# E3.net
KiCad netlist of a schematic drawn in Altium Designer
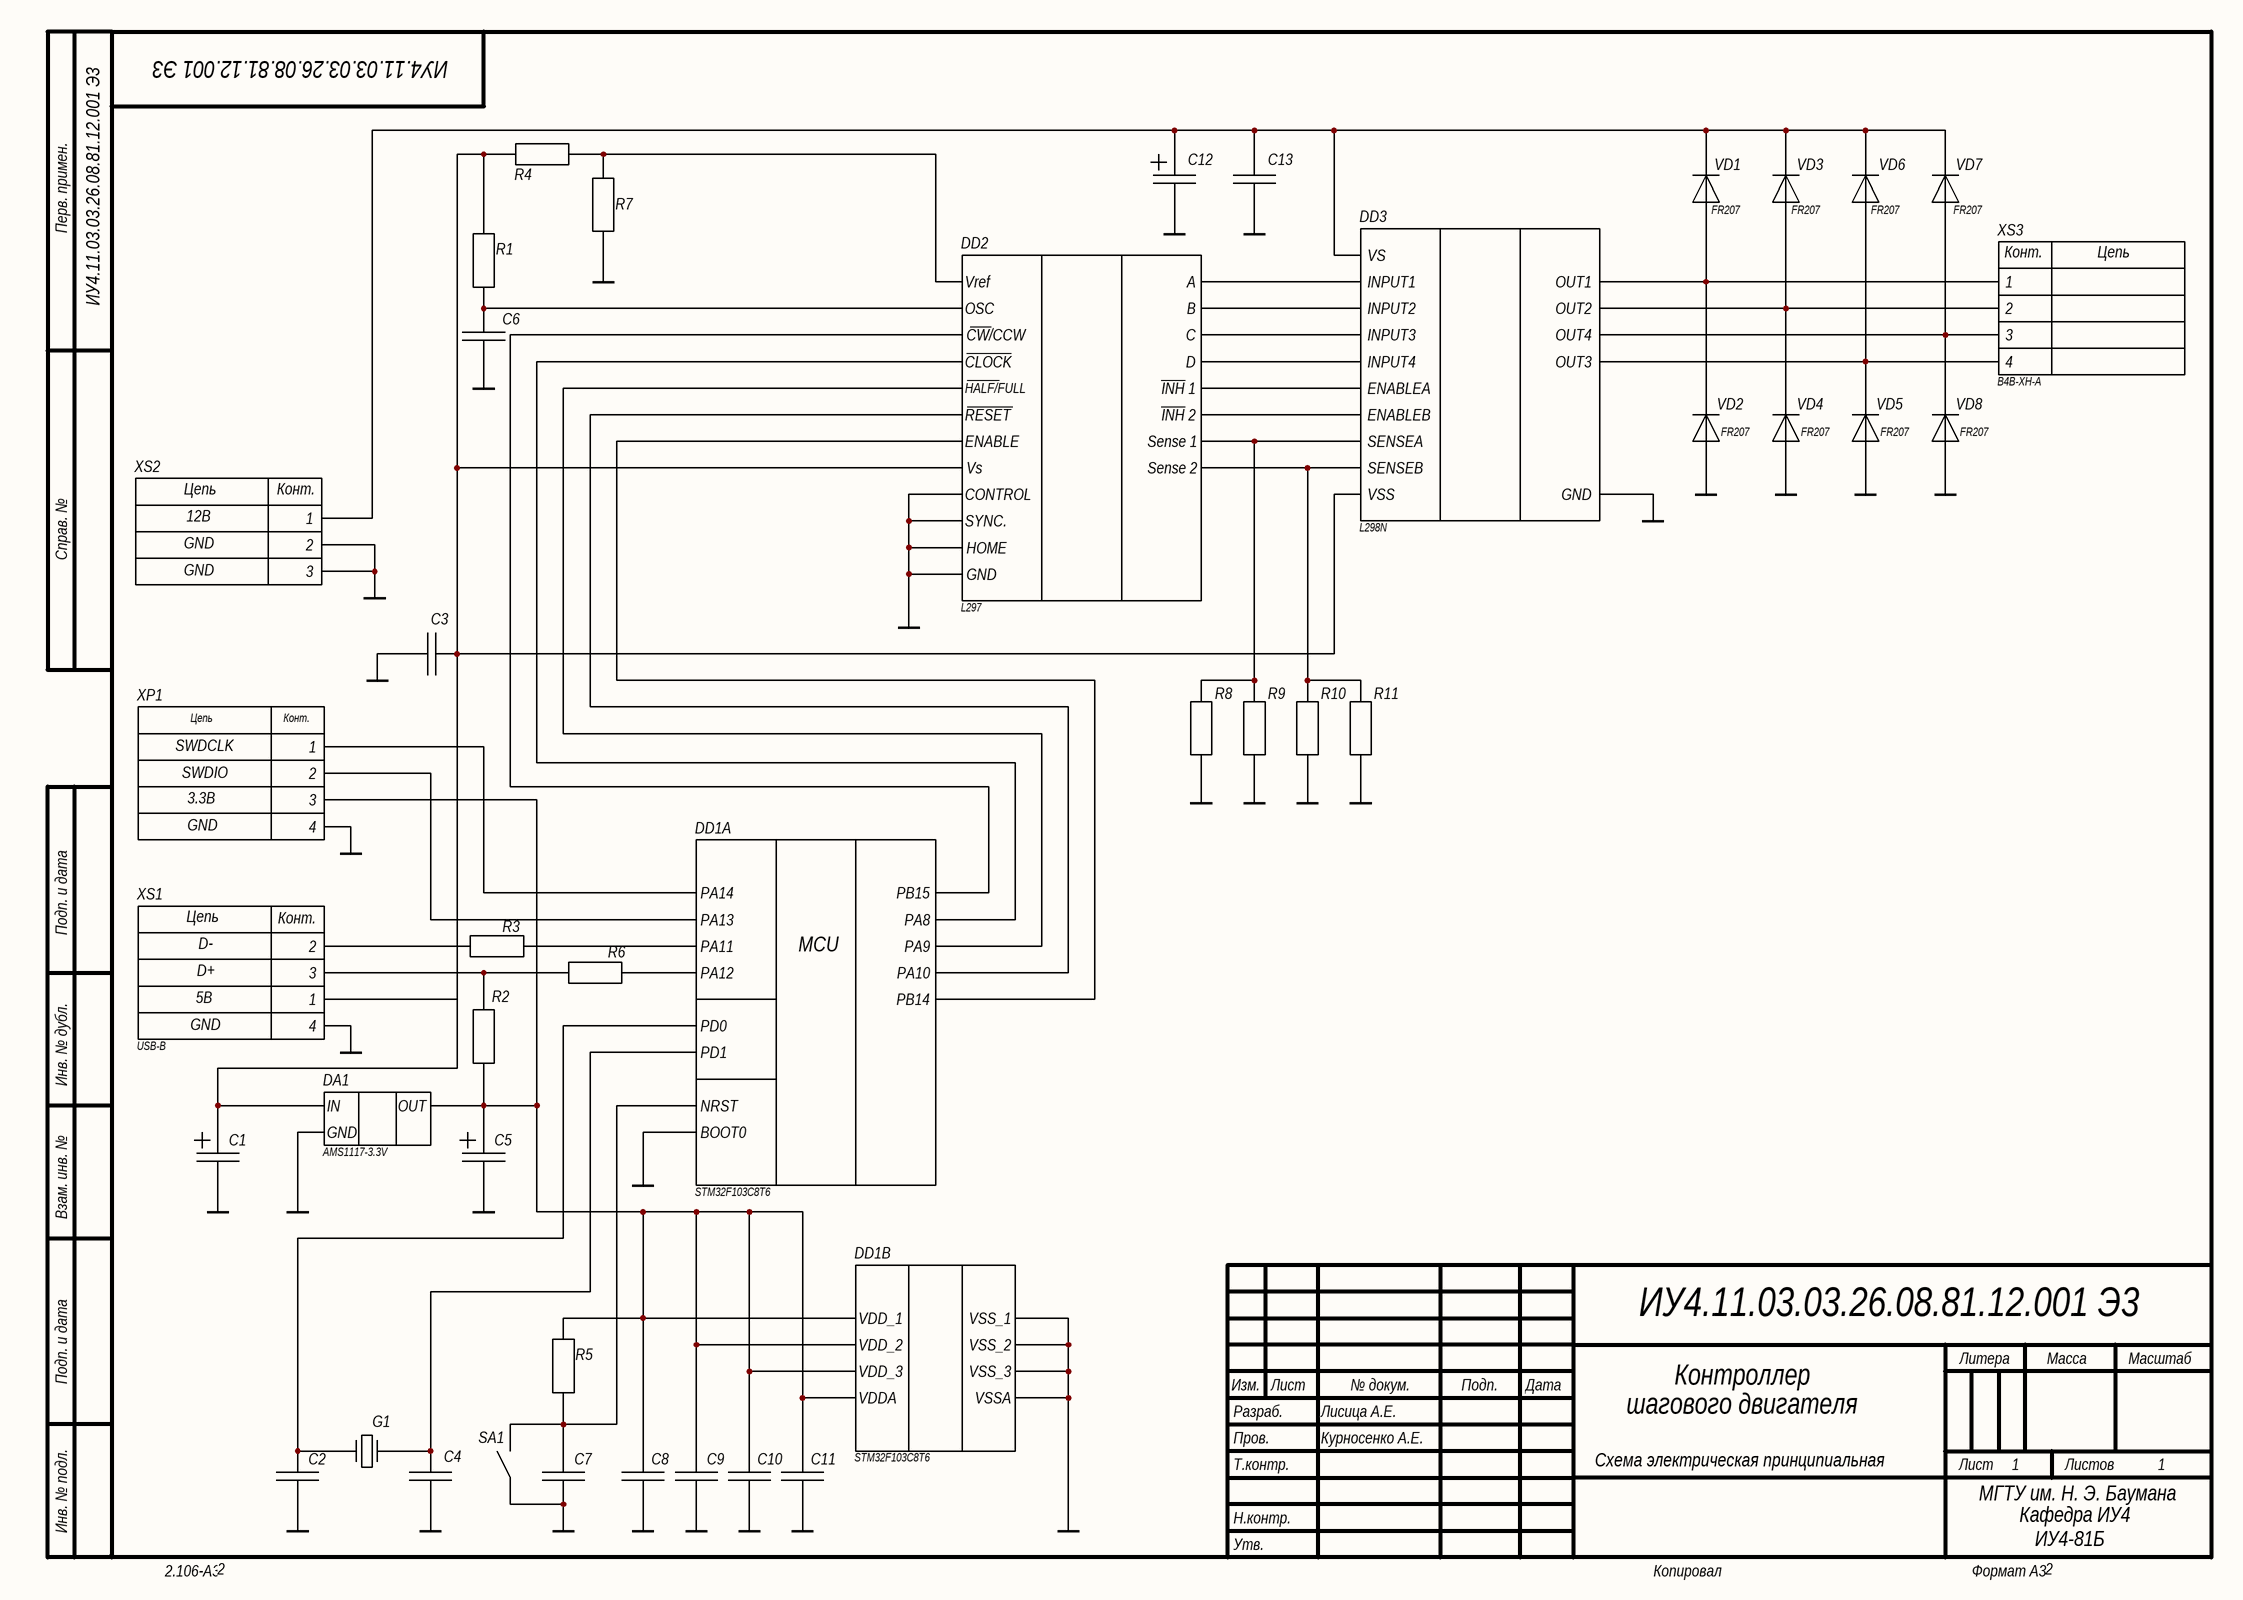
[diagram p0: E3.SchDoc]

(export (version "E")
  (design (tool "Eeschema 10.0.6"))
  (components
    (comp (ref "C1")
      (value "47uF")
      (footprint "ECAPT_6032(C)")
      (description "Tantalum_SMD")
      (libsource (lib "Capacitors_GOST") (part "ECAPT_6032"))
    )
    (comp (ref "C2")
      (value "CAP_SMD_1206")
      (footprint "CAP_0603")
      (libsource (lib "Capacitors_GOST") (part "CAP_SMD_1206"))
    )
    (comp (ref "C3")
      (value "CAP_SMD_1206")
      (footprint "CAP_0603")
      (libsource (lib "Capacitors_GOST") (part "CAP_SMD_1206"))
    )
    (comp (ref "C4")
      (value "CAP_SMD_1206")
      (footprint "CAP_0603")
      (libsource (lib "Capacitors_GOST") (part "CAP_SMD_1206"))
    )
    (comp (ref "C5")
      (value "22uF")
      (footprint "ECAPT_6032(C)")
      (description "Tantalum_SMD")
      (libsource (lib "Capacitors_GOST") (part "ECAPT_6032"))
    )
    (comp (ref "C6")
      (value "CAP_SMD_1206")
      (footprint "CAP_0603")
      (libsource (lib "Capacitors_GOST") (part "CAP_SMD_1206"))
    )
    (comp (ref "C7")
      (value "CAP_SMD_1206")
      (footprint "CAP_0603")
      (libsource (lib "Capacitors_GOST") (part "CAP_SMD_1206"))
    )
    (comp (ref "C8")
      (value "CAP_SMD_1206")
      (footprint "CAP_0603")
      (libsource (lib "Capacitors_GOST") (part "CAP_SMD_1206"))
    )
    (comp (ref "C9")
      (value "CAP_SMD_1206")
      (footprint "CAP_0603")
      (libsource (lib "Capacitors_GOST") (part "CAP_SMD_1206"))
    )
    (comp (ref "C10")
      (value "CAP_SMD_1206")
      (footprint "CAP_0603")
      (libsource (lib "Capacitors_GOST") (part "CAP_SMD_1206"))
    )
    (comp (ref "C11")
      (value "CAP_SMD_1206")
      (footprint "CAP_0603")
      (libsource (lib "Capacitors_GOST") (part "CAP_SMD_1206"))
    )
    (comp (ref "C12")
      (value "ECAP_10×10.2_SMD")
      (footprint "ECAP_SMD_10x10.2")
      (libsource (lib "Capacitors_GOST") (part "ECAP_10×10.2_SMD"))
    )
    (comp (ref "C13")
      (value "CAP_SMD_1206")
      (footprint "CAP_1206(SMD)")
      (libsource (lib "Capacitors_GOST") (part "CAP_SMD_1206"))
    )
    (comp (ref "DA1")
      (value "AMS1117-3.3V")
      (footprint "SOT-223")
      (description "800mA LOW DROPOUT VOLTAGE REGULATOR SOT-223 PACKAGE")
      (libsource (lib "Microschemes_GOST") (part "AMS1117-3.3V"))
    )
    (comp (ref "DD1")
      (value "STM32F103C8T6")
      (footprint "LQFP48_STM-L")
      (description "ARM microcontroller; Flash: 64kB; 72MHz; SRAM: 20kB; LQFP48")
      (libsource (lib "Microschemes_GOST") (part "STM32F103C8T6_Stepper"))
    )
    (comp (ref "DD2")
      (value "L297")
      (footprint "SO-20_STM")
      (libsource (lib "Microschemes_GOST") (part "L297_SO20"))
    )
    (comp (ref "DD3")
      (value "L298N")
      (footprint "Multiwatt15_V_STM")
      (description "DUAL FULL-BRIDGE DRIVER")
      (libsource (lib "Microschemes_GOST") (part "L298N"))
    )
    (comp (ref "G1")
      (value "OSC8MHz")
      (footprint "OSC8MHz")
      (libsource (lib "Oscillators_GOST") (part "OSC8MHz"))
    )
    (comp (ref "R1")
      (value "22k")
      (footprint "RES_1206(SMD)")
      (libsource (lib "Resistors_GOST") (part "RES_SMD_1206"))
    )
    (comp (ref "R2")
      (value "1.5к")
      (footprint "RES_1206(SMD)")
      (libsource (lib "Resistors_GOST") (part "RES_SMD_1206"))
    )
    (comp (ref "R3")
      (value "22 Omh")
      (footprint "RES_1206(SMD)")
      (description "20 Omh")
      (libsource (lib "Resistors_GOST") (part "RES_SMD_1206"))
    )
    (comp (ref "R4")
      (value "10k")
      (footprint "RES_1206(SMD)")
      (libsource (lib "Resistors_GOST") (part "RES_SMD_1206"))
    )
    (comp (ref "R5")
      (value "10k")
      (footprint "RES_1206(SMD)")
      (libsource (lib "Resistors_GOST") (part "RES_SMD_1206"))
    )
    (comp (ref "R6")
      (value "22 Omh")
      (footprint "RES_1206(SMD)")
      (description "20 Omh")
      (libsource (lib "Resistors_GOST") (part "RES_SMD_1206"))
    )
    (comp (ref "R7")
      (value "2.4k")
      (footprint "RES_1206(SMD)")
      (libsource (lib "Resistors_GOST") (part "RES_SMD_1206"))
    )
    (comp (ref "R8")
      (value "1 Ом")
      (footprint "RES_2512(SMD)")
      (libsource (lib "Resistors_GOST") (part "RES_2512"))
    )
    (comp (ref "R9")
      (value "1 Ом")
      (footprint "RES_2512(SMD)")
      (libsource (lib "Resistors_GOST") (part "RES_2512"))
    )
    (comp (ref "R10")
      (value "1 Ом")
      (footprint "RES_2512(SMD)")
      (libsource (lib "Resistors_GOST") (part "RES_2512"))
    )
    (comp (ref "R11")
      (value "1 Ом")
      (footprint "RES_2512(SMD)")
      (libsource (lib "Resistors_GOST") (part "RES_2512"))
    )
    (comp (ref "SA1") (value "button") (libsource (lib "Connectors_GOST") (part "button")))
    (comp (ref "VD1") (value "FR207") (footprint "THT_DIODE") (libsource (lib "Diodes_GOST") (part "FR207")))
    (comp (ref "VD2") (value "FR207") (footprint "THT_DIODE") (libsource (lib "Diodes_GOST") (part "FR207")))
    (comp (ref "VD3") (value "FR207") (footprint "THT_DIODE") (libsource (lib "Diodes_GOST") (part "FR207")))
    (comp (ref "VD4") (value "FR207") (footprint "THT_DIODE") (libsource (lib "Diodes_GOST") (part "FR207")))
    (comp (ref "VD5") (value "FR207") (footprint "THT_DIODE") (libsource (lib "Diodes_GOST") (part "FR207")))
    (comp (ref "VD6") (value "FR207") (footprint "THT_DIODE") (libsource (lib "Diodes_GOST") (part "FR207")))
    (comp (ref "VD7") (value "FR207") (footprint "THT_DIODE") (libsource (lib "Diodes_GOST") (part "FR207")))
    (comp (ref "VD8") (value "FR207") (footprint "THT_DIODE") (libsource (lib "Diodes_GOST") (part "FR207")))
    (comp (ref "XP1") (value "PLS-4") (footprint "PLS2-4") (libsource (lib "Connectors_GOST") (part "SWD")))
    (comp (ref "XS1")
      (value "USB-B")
      (footprint "USB_B_FEMALE")
      (description "SOCKET 4PIN USB B 2.0")
      (libsource (lib "Connectors_GOST") (part "USB_B"))
    )
    (comp (ref "XS2")
      (value "POWER")
      (footprint "2.5 x 6.5 mm32")
      (libsource (lib "Connectors_GOST") (part "POWER"))
    )
    (comp (ref "XS3")
      (value "B4B-XH-A")
      (footprint "B4B-XH-A")
      (description "SOCKET 4PIN, вилка прямая на плату")
      (libsource (lib "Connectors_GOST") (part "B4B-XH-A"))
    )
  )
  (nets
    (net (code "1") (name "GND") (class "Default")
      (node (ref "C1") (pin "2") (pinfunction "2_2") (pintype "passive"))
      (node (ref "C10") (pin "2") (pinfunction "2_2") (pintype "passive"))
      (node (ref "C11") (pin "2") (pinfunction "2_2") (pintype "passive"))
      (node (ref "C12") (pin "1") (pinfunction "2_1") (pintype "passive"))
      (node (ref "C13") (pin "2") (pinfunction "2_2") (pintype "passive"))
      (node (ref "C2") (pin "2") (pinfunction "2_2") (pintype "passive"))
      (node (ref "C3") (pin "1") (pinfunction "1_1") (pintype "passive"))
      (node (ref "C4") (pin "2") (pinfunction "2_2") (pintype "passive"))
      (node (ref "C5") (pin "2") (pinfunction "2_2") (pintype "passive"))
      (node (ref "C6") (pin "2") (pinfunction "2_2") (pintype "passive"))
      (node (ref "C7") (pin "1") (pinfunction "1_1") (pintype "passive"))
      (node (ref "C8") (pin "2") (pinfunction "2_2") (pintype "passive"))
      (node (ref "C9") (pin "2") (pinfunction "2_2") (pintype "passive"))
      (node (ref "DA1") (pin "1") (pinfunction "GND_1") (pintype "passive"))
      (node (ref "DD1") (pin "23") (pinfunction "VSS_1_23") (pintype "passive"))
      (node (ref "DD1") (pin "35") (pinfunction "VSS_2_35") (pintype "passive"))
      (node (ref "DD1") (pin "44") (pinfunction "BOOT0_44") (pintype "passive"))
      (node (ref "DD1") (pin "47") (pinfunction "VSS_3_47") (pintype "passive"))
      (node (ref "DD1") (pin "8") (pinfunction "VSSA_8") (pintype "passive"))
      (node (ref "DD2") (pin "1") (pinfunction "SYNC._1") (pintype "passive"))
      (node (ref "DD2") (pin "11") (pinfunction "CONTROL_11") (pintype "passive"))
      (node (ref "DD2") (pin "2") (pinfunction "GND_2") (pintype "passive"))
      (node (ref "DD2") (pin "3") (pinfunction "HOME_3") (pintype "passive"))
      (node (ref "DD3") (pin "8") (pinfunction "GND_8") (pintype "power_in"))
      (node (ref "R10") (pin "2") (pinfunction "2_2") (pintype "passive"))
      (node (ref "R11") (pin "2") (pinfunction "2_2") (pintype "passive"))
      (node (ref "R7") (pin "2") (pinfunction "2_2") (pintype "passive"))
      (node (ref "R8") (pin "2") (pinfunction "2_2") (pintype "passive"))
      (node (ref "R9") (pin "2") (pinfunction "2_2") (pintype "passive"))
      (node (ref "SA1") (pin "1") (pinfunction "1_1") (pintype "passive"))
      (node (ref "VD2") (pin "1") (pinfunction "1_1") (pintype "passive"))
      (node (ref "VD4") (pin "1") (pinfunction "1_1") (pintype "passive"))
      (node (ref "VD5") (pin "1") (pinfunction "1_1") (pintype "passive"))
      (node (ref "VD8") (pin "1") (pinfunction "1_1") (pintype "passive"))
      (node (ref "XP1") (pin "4") (pinfunction "4_4") (pintype "passive"))
      (node (ref "XS1") (pin "4") (pinfunction "4_4") (pintype "passive"))
      (node (ref "XS2") (pin "2") (pinfunction "2_2") (pintype "passive"))
      (node (ref "XS2") (pin "3") (pinfunction "3_3") (pintype "passive"))
    )
    (net (code "2") (name "Net-(DA1-IN)") (class "Default")
      (node (ref "C1") (pin "1") (pinfunction "1_1") (pintype "passive"))
      (node (ref "C3") (pin "2") (pinfunction "2_2") (pintype "passive"))
      (node (ref "DA1") (pin "3") (pinfunction "IN_3") (pintype "passive"))
      (node (ref "DD2") (pin "12") (pinfunction "Vs_12") (pintype "passive"))
      (node (ref "DD3") (pin "9") (pinfunction "VSS_9") (pintype "power_in"))
      (node (ref "R1") (pin "2") (pinfunction "2_2") (pintype "passive"))
      (node (ref "R4") (pin "1") (pinfunction "1_1") (pintype "passive"))
      (node (ref "XS1") (pin "1") (pinfunction "1_1") (pintype "passive"))
    )
    (net (code "3") (name "Net-(DA1-OUT)") (class "Default")
      (node (ref "C10") (pin "1") (pinfunction "1_1") (pintype "passive"))
      (node (ref "C11") (pin "1") (pinfunction "1_1") (pintype "passive"))
      (node (ref "C5") (pin "1") (pinfunction "1_1") (pintype "passive"))
      (node (ref "C8") (pin "1") (pinfunction "1_1") (pintype "passive"))
      (node (ref "C9") (pin "1") (pinfunction "1_1") (pintype "passive"))
      (node (ref "DA1") (pin "2") (pinfunction "OUT_2") (pintype "passive"))
      (node (ref "DD1") (pin "24") (pinfunction "VDD_1_24") (pintype "passive"))
      (node (ref "DD1") (pin "36") (pinfunction "VDD_2_36") (pintype "passive"))
      (node (ref "DD1") (pin "48") (pinfunction "VDD_3_48") (pintype "passive"))
      (node (ref "DD1") (pin "9") (pinfunction "VDDA_9") (pintype "passive"))
      (node (ref "R2") (pin "2") (pinfunction "2_2") (pintype "passive"))
      (node (ref "R5") (pin "2") (pinfunction "2_2") (pintype "passive"))
      (node (ref "XP1") (pin "3") (pinfunction "3_3") (pintype "passive"))
    )
    (net (code "4") (name "Net-(DD1A-NRST)") (class "Default")
      (node (ref "C7") (pin "2") (pinfunction "2_2") (pintype "passive"))
      (node (ref "DD1") (pin "7") (pinfunction "NRST_7") (pintype "passive"))
      (node (ref "R5") (pin "1") (pinfunction "1_1") (pintype "passive"))
      (node (ref "SA1") (pin "2") (pinfunction "2_2") (pintype "passive"))
    )
    (net (code "5") (name "Net-(DD1A-PA8)") (class "Default")
      (node (ref "DD1") (pin "29") (pinfunction "PA8_29") (pintype "passive"))
      (node (ref "DD2") (pin "18") (pinfunction "CLOCK_18") (pintype "passive"))
    )
    (net (code "6") (name "Net-(DD1A-PA9)") (class "Default")
      (node (ref "DD1") (pin "30") (pinfunction "PA9_30") (pintype "passive"))
      (node (ref "DD2") (pin "19") (pinfunction "HALF/FULL_19") (pintype "passive"))
    )
    (net (code "7") (name "Net-(DD1A-PA10)") (class "Default")
      (node (ref "DD1") (pin "31") (pinfunction "PA10_31") (pintype "passive"))
      (node (ref "DD2") (pin "20") (pinfunction "RESET_20") (pintype "passive"))
    )
    (net (code "8") (name "Net-(DD1A-PA11)") (class "Default")
      (node (ref "DD1") (pin "32") (pinfunction "PA11_32") (pintype "passive"))
      (node (ref "R3") (pin "1") (pinfunction "1_1") (pintype "passive"))
    )
    (net (code "9") (name "Net-(DD1A-PA12)") (class "Default")
      (node (ref "DD1") (pin "33") (pinfunction "PA12_33") (pintype "passive"))
      (node (ref "R6") (pin "1") (pinfunction "1_1") (pintype "passive"))
    )
    (net (code "10") (name "Net-(DD1A-PA13)") (class "Default")
      (node (ref "DD1") (pin "34") (pinfunction "PA13_34") (pintype "passive"))
      (node (ref "XP1") (pin "2") (pinfunction "2_2") (pintype "passive"))
    )
    (net (code "11") (name "Net-(DD1A-PA14)") (class "Default")
      (node (ref "DD1") (pin "37") (pinfunction "PA14_37") (pintype "passive"))
      (node (ref "XP1") (pin "1") (pinfunction "1_1") (pintype "passive"))
    )
    (net (code "12") (name "Net-(DD1A-PB14)") (class "Default")
      (node (ref "DD1") (pin "27") (pinfunction "PB14_27") (pintype "passive"))
      (node (ref "DD2") (pin "10") (pinfunction "ENABLE_10") (pintype "passive"))
    )
    (net (code "13") (name "Net-(DD1A-PB15)") (class "Default")
      (node (ref "DD1") (pin "28") (pinfunction "PB15_28") (pintype "passive"))
      (node (ref "DD2") (pin "17") (pinfunction "CW/CCW_17") (pintype "passive"))
    )
    (net (code "14") (name "Net-(DD1A-PD0)") (class "Default")
      (node (ref "C2") (pin "1") (pinfunction "1_1") (pintype "passive"))
      (node (ref "DD1") (pin "5") (pinfunction "PD0_5") (pintype "passive"))
      (node (ref "G1") (pin "2") (pinfunction "output_2") (pintype "passive"))
    )
    (net (code "15") (name "Net-(DD1A-PD1)") (class "Default")
      (node (ref "C4") (pin "1") (pinfunction "1_1") (pintype "passive"))
      (node (ref "DD1") (pin "6") (pinfunction "PD1_6") (pintype "passive"))
      (node (ref "G1") (pin "1") (pinfunction "input_1") (pintype "passive"))
    )
    (net (code "16") (name "Net-(DD2-A)") (class "Default")
      (node (ref "DD2") (pin "4") (pinfunction "A_4") (pintype "passive"))
      (node (ref "DD3") (pin "5") (pinfunction "INPUT1_5") (pintype "power_in"))
    )
    (net (code "17") (name "Net-(DD2-B)") (class "Default")
      (node (ref "DD2") (pin "6") (pinfunction "B_6") (pintype "passive"))
      (node (ref "DD3") (pin "7") (pinfunction "INPUT2_7") (pintype "power_in"))
    )
    (net (code "18") (name "Net-(DD2-C)") (class "Default")
      (node (ref "DD2") (pin "7") (pinfunction "C_7") (pintype "passive"))
      (node (ref "DD3") (pin "10") (pinfunction "INPUT3_10") (pintype "power_in"))
    )
    (net (code "19") (name "Net-(DD2-D)") (class "Default")
      (node (ref "DD2") (pin "9") (pinfunction "D_9") (pintype "passive"))
      (node (ref "DD3") (pin "12") (pinfunction "INPUT4_12") (pintype "power_in"))
    )
    (net (code "20") (name "Net-(DD2-INH_1)") (class "Default")
      (node (ref "DD2") (pin "5") (pinfunction "INH_1_5") (pintype "passive"))
      (node (ref "DD3") (pin "6") (pinfunction "ENABLEA_6") (pintype "power_in"))
    )
    (net (code "21") (name "Net-(DD2-INH_2)") (class "Default")
      (node (ref "DD2") (pin "8") (pinfunction "INH_2_8") (pintype "passive"))
      (node (ref "DD3") (pin "11") (pinfunction "ENABLEB_11") (pintype "power_in"))
    )
    (net (code "22") (name "Net-(DD2-OSC)") (class "Default")
      (node (ref "C6") (pin "1") (pinfunction "1_1") (pintype "passive"))
      (node (ref "DD2") (pin "16") (pinfunction "OSC_16") (pintype "passive"))
      (node (ref "R1") (pin "1") (pinfunction "1_1") (pintype "passive"))
    )
    (net (code "23") (name "Net-(DD2-Sense_1)") (class "Default")
      (node (ref "DD2") (pin "14") (pinfunction "Sense_1_14") (pintype "passive"))
      (node (ref "DD3") (pin "1") (pinfunction "SENSEA_1") (pintype "power_in"))
      (node (ref "R8") (pin "1") (pinfunction "1_1") (pintype "passive"))
      (node (ref "R9") (pin "1") (pinfunction "1_1") (pintype "passive"))
    )
    (net (code "24") (name "Net-(DD2-Sense_2)") (class "Default")
      (node (ref "DD2") (pin "13") (pinfunction "Sense_2_13") (pintype "passive"))
      (node (ref "DD3") (pin "15") (pinfunction "SENSEB_15") (pintype "power_in"))
      (node (ref "R10") (pin "1") (pinfunction "1_1") (pintype "passive"))
      (node (ref "R11") (pin "1") (pinfunction "1_1") (pintype "passive"))
    )
    (net (code "25") (name "Net-(DD2-Vref)") (class "Default")
      (node (ref "DD2") (pin "15") (pinfunction "Vref_15") (pintype "passive"))
      (node (ref "R4") (pin "2") (pinfunction "2_2") (pintype "passive"))
      (node (ref "R7") (pin "1") (pinfunction "1_1") (pintype "passive"))
    )
    (net (code "26") (name "Net-(DD3-OUT1)") (class "Default")
      (node (ref "DD3") (pin "2") (pinfunction "OUT1_2") (pintype "power_in"))
      (node (ref "VD1") (pin "1") (pinfunction "1_1") (pintype "passive"))
      (node (ref "VD2") (pin "2") (pinfunction "2_2") (pintype "passive"))
      (node (ref "XS3") (pin "1") (pinfunction "1_1") (pintype "passive"))
    )
    (net (code "27") (name "Net-(DD3-OUT2)") (class "Default")
      (node (ref "DD3") (pin "3") (pinfunction "OUT2_3") (pintype "power_in"))
      (node (ref "VD3") (pin "1") (pinfunction "1_1") (pintype "passive"))
      (node (ref "VD4") (pin "2") (pinfunction "2_2") (pintype "passive"))
      (node (ref "XS3") (pin "2") (pinfunction "2_2") (pintype "passive"))
    )
    (net (code "28") (name "Net-(DD3-OUT3)") (class "Default")
      (node (ref "DD3") (pin "13") (pinfunction "OUT3_13") (pintype "power_in"))
      (node (ref "VD5") (pin "2") (pinfunction "2_2") (pintype "passive"))
      (node (ref "VD6") (pin "1") (pinfunction "1_1") (pintype "passive"))
      (node (ref "XS3") (pin "4") (pinfunction "4_4") (pintype "passive"))
    )
    (net (code "29") (name "Net-(DD3-OUT4)") (class "Default")
      (node (ref "DD3") (pin "14") (pinfunction "OUT4_14") (pintype "power_in"))
      (node (ref "VD7") (pin "1") (pinfunction "1_1") (pintype "passive"))
      (node (ref "VD8") (pin "2") (pinfunction "2_2") (pintype "passive"))
      (node (ref "XS3") (pin "3") (pinfunction "3_3") (pintype "passive"))
    )
    (net (code "30") (name "Net-(DD3-VS)") (class "Default")
      (node (ref "C12") (pin "2") (pintype "passive"))
      (node (ref "C13") (pin "1") (pinfunction "1_1") (pintype "passive"))
      (node (ref "DD3") (pin "4") (pinfunction "VS_4") (pintype "power_in"))
      (node (ref "VD1") (pin "2") (pinfunction "2_2") (pintype "passive"))
      (node (ref "VD3") (pin "2") (pinfunction "2_2") (pintype "passive"))
      (node (ref "VD6") (pin "2") (pinfunction "2_2") (pintype "passive"))
      (node (ref "VD7") (pin "2") (pinfunction "2_2") (pintype "passive"))
      (node (ref "XS2") (pin "1") (pinfunction "1_1") (pintype "passive"))
    )
    (net (code "31") (name "Net-(R2-Pad1)") (class "Default")
      (node (ref "R2") (pin "1") (pinfunction "1_1") (pintype "passive"))
      (node (ref "R6") (pin "2") (pinfunction "2_2") (pintype "passive"))
      (node (ref "XS1") (pin "3") (pinfunction "3_3") (pintype "passive"))
    )
    (net (code "32") (name "Net-(R3-Pad2)") (class "Default")
      (node (ref "R3") (pin "2") (pinfunction "2_2") (pintype "passive"))
      (node (ref "XS1") (pin "2") (pinfunction "2_2") (pintype "passive"))
    )
  )
)
